# E77R.net
KiCad netlist of a schematic drawn in Altium Designer
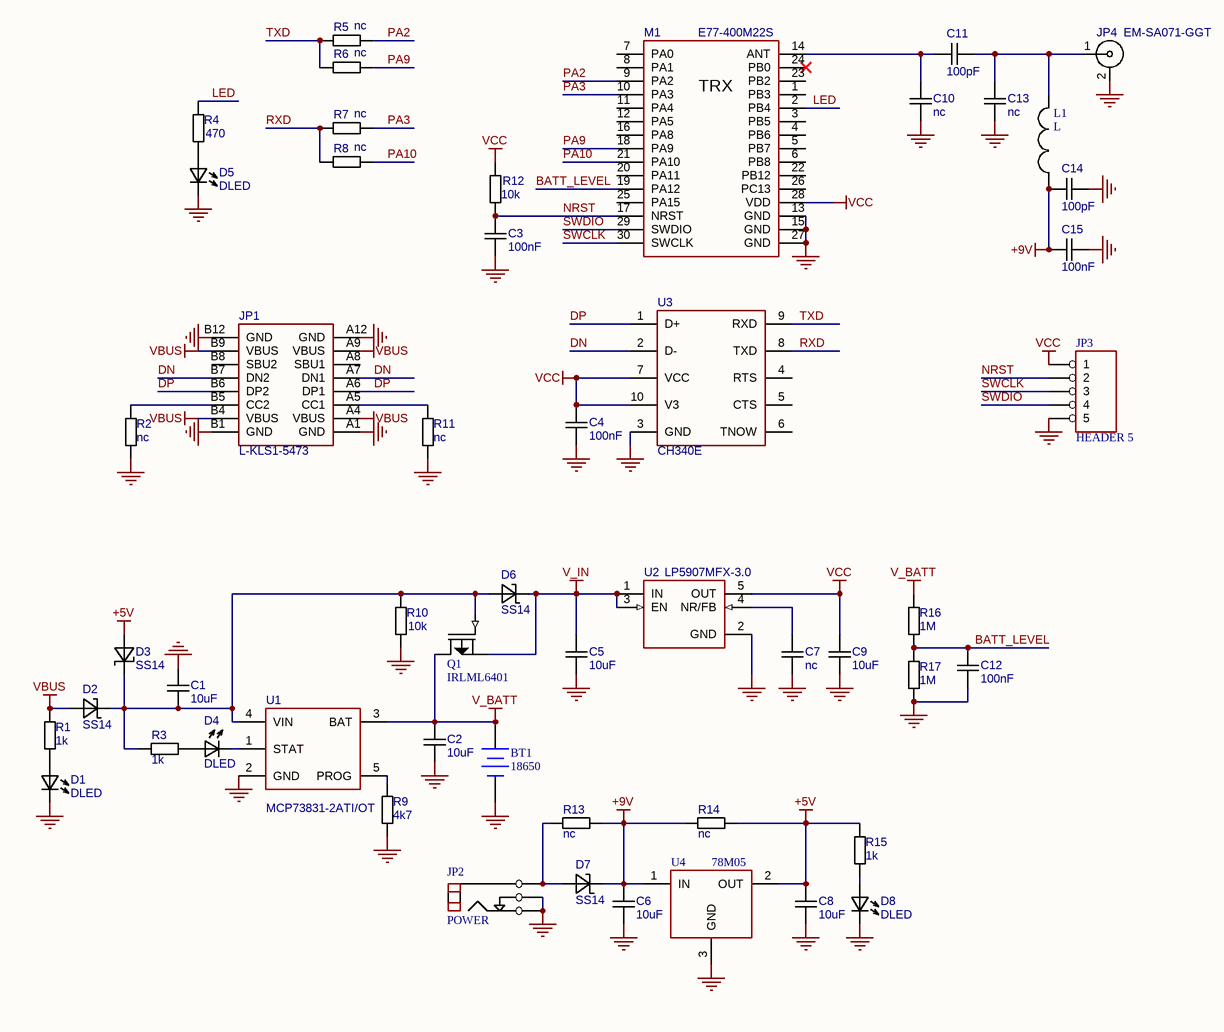
[diagram p0: E77R.SchDoc]

(export (version "E")
  (design (tool "Eeschema 10.0.6"))
  (components
    (comp (ref "BT1")
      (value "18650")
      (footprint "18650")
      (description "Multicell Battery")
      (fields (field (name "PUBLISHER") "Altium Limited"))
      (libsource (lib "zucker") (part "Battery"))
    )
    (comp (ref "C1")
      (value "10uF")
      (footprint "C-0805")
      (fields (field (name "VOLTAGE") "50V"))
      (libsource (lib "Passive") (part "CAPN"))
    )
    (comp (ref "C2")
      (value "10uF")
      (footprint "C-0805")
      (fields (field (name "VOLTAGE") "50V"))
      (libsource (lib "Passive") (part "CAPN"))
    )
    (comp (ref "C3")
      (value "100nF")
      (footprint "C-0603")
      (fields (field (name "VOLTAGE") "50V"))
      (libsource (lib "Passive") (part "CAPN"))
    )
    (comp (ref "C4")
      (value "100nF")
      (footprint "C-0603")
      (fields (field (name "VOLTAGE") "50V"))
      (libsource (lib "Passive") (part "CAPN"))
    )
    (comp (ref "C5")
      (value "10uF")
      (footprint "C-0805")
      (fields (field (name "VOLTAGE") "50V"))
      (libsource (lib "Passive") (part "CAPN"))
    )
    (comp (ref "C6")
      (value "10uF")
      (footprint "C-0805")
      (fields (field (name "VOLTAGE") "50V"))
      (libsource (lib "Passive") (part "CAPN"))
    )
    (comp (ref "C7")
      (value "nc")
      (footprint "C-0603")
      (fields (field (name "VOLTAGE") "50V"))
      (libsource (lib "Passive") (part "CAPN"))
    )
    (comp (ref "C8")
      (value "10uF")
      (footprint "C-0805")
      (fields (field (name "VOLTAGE") "50V"))
      (libsource (lib "Passive") (part "CAPN"))
    )
    (comp (ref "C9")
      (value "10uF")
      (footprint "C-0805")
      (fields (field (name "VOLTAGE") "50V"))
      (libsource (lib "Passive") (part "CAPN"))
    )
    (comp (ref "C10")
      (value "nc")
      (footprint "C-0603")
      (fields (field (name "VOLTAGE") "50V"))
      (libsource (lib "Passive") (part "CAPN"))
    )
    (comp (ref "C11")
      (value "100pF")
      (footprint "C-0603")
      (fields (field (name "VOLTAGE") "50V"))
      (libsource (lib "Passive") (part "CAPN"))
    )
    (comp (ref "C12")
      (value "100nF")
      (footprint "C-0603")
      (fields (field (name "VOLTAGE") "50V"))
      (libsource (lib "Passive") (part "CAPN"))
    )
    (comp (ref "C13")
      (value "nc")
      (footprint "C-0603")
      (fields (field (name "VOLTAGE") "50V"))
      (libsource (lib "Passive") (part "CAPN"))
    )
    (comp (ref "C14")
      (value "100pF")
      (footprint "C-0603")
      (fields (field (name "VOLTAGE") "50V"))
      (libsource (lib "Passive") (part "CAPN"))
    )
    (comp (ref "C15")
      (value "100nF")
      (footprint "C-0603")
      (fields (field (name "VOLTAGE") "50V"))
      (libsource (lib "Passive") (part "CAPN"))
    )
    (comp (ref "D1") (value "DLED") (footprint "LED0805") (libsource (lib "Diodes") (part "DLED")))
    (comp (ref "D2") (value "SS14") (footprint "D-SMA") (libsource (lib "Diodes") (part "DIODSH")))
    (comp (ref "D3") (value "SS14") (footprint "D-SMA") (libsource (lib "Diodes") (part "DIODSH")))
    (comp (ref "D4") (value "DLED") (footprint "LED0805") (libsource (lib "Diodes") (part "DLED")))
    (comp (ref "D5") (value "DLED") (footprint "LED0805") (libsource (lib "Diodes") (part "DLED")))
    (comp (ref "D6") (value "SS14") (footprint "D-SMA") (libsource (lib "Diodes") (part "DIODSH")))
    (comp (ref "D7") (value "SS14") (footprint "D-SMA") (libsource (lib "Diodes") (part "DIODSH")))
    (comp (ref "D8") (value "DLED") (footprint "LED0805") (libsource (lib "Diodes") (part "DLED")))
    (comp (ref "JP1")
      (value "L-KLS1-5473")
      (footprint "USB_C_SMD_SLOT")
      (libsource (lib "Connectors") (part "L-KLS1-5473"))
    )
    (comp (ref "JP2") (value "POWER") (footprint "DC-140-003") (libsource (lib "Connectors") (part "POWER")))
    (comp (ref "JP3")
      (value "HEADER 5")
      (footprint "PLS1-5")
      (libsource (lib "Connectors") (part "HEADER 5"))
    )
    (comp (ref "JP4")
      (value "EM-SA071-GGT")
      (footprint "SMA_F_EDGE")
      (description "SMA Female R/A PCB Mount")
      (libsource (lib "Connectors") (part "SMA"))
    )
    (comp (ref "L1") (value "L") (footprint "SCI1812") (libsource (lib "Passive") (part "L")))
    (comp (ref "M1")
      (value "E77-400M22S")
      (footprint "E77XX-M22")
      (libsource (lib "RFmodules") (part "E77-400M22S"))
    )
    (comp (ref "Q1") (value "IRLML6401") (footprint "SOT-23") (libsource (lib "Discrete") (part "MOSF-P")))
    (comp (ref "R1") (value "1k") (footprint "R-0603") (libsource (lib "") (part "RES_1")))
    (comp (ref "R2") (value "nc") (footprint "R-0603") (libsource (lib "") (part "RES_3")))
    (comp (ref "R3") (value "1k") (footprint "R-0603") (libsource (lib "") (part "RES_2")))
    (comp (ref "R4") (value "470") (footprint "R-0603") (libsource (lib "") (part "RES_1")))
    (comp (ref "R5") (value "nc") (footprint "R-0603") (libsource (lib "Passive") (part "RES")))
    (comp (ref "R6") (value "nc") (footprint "R-0603") (libsource (lib "Passive") (part "RES")))
    (comp (ref "R7") (value "nc") (footprint "R-0603") (libsource (lib "Passive") (part "RES")))
    (comp (ref "R8") (value "nc") (footprint "R-0603") (libsource (lib "Passive") (part "RES")))
    (comp (ref "R9") (value "4k7") (footprint "R-0603") (libsource (lib "") (part "RES_1")))
    (comp (ref "R10") (value "10k") (footprint "R-0603") (libsource (lib "") (part "RES_1")))
    (comp (ref "R11") (value "nc") (footprint "R-0603") (libsource (lib "") (part "RES_3")))
    (comp (ref "R12") (value "10k") (footprint "R-0603") (libsource (lib "") (part "RES_1")))
    (comp (ref "R13") (value "nc") (footprint "R-0805") (libsource (lib "Passive") (part "RES")))
    (comp (ref "R14") (value "nc") (footprint "R-0805") (libsource (lib "Passive") (part "RES")))
    (comp (ref "R15") (value "1k") (footprint "R-0603") (libsource (lib "") (part "RES_1")))
    (comp (ref "R16") (value "1M") (footprint "R-0603") (libsource (lib "") (part "RES_1")))
    (comp (ref "R17") (value "1M") (footprint "R-0603") (libsource (lib "") (part "RES_1")))
    (comp (ref "U1")
      (value "MCP73831-2ATI/OT")
      (footprint "SOT-23-5")
      (fields
        (field (name "LIBRARY PART") "IC`s.SchLib")
        (field (name "FOOTPRINT PART") "IC-package.PcbLib")
        (field (name "MANUFACTURER") "Texas Instruments")
      )
      (libsource (lib "ICs") (part "MCP73831-2ATI/OT"))
    )
    (comp (ref "U2")
      (value "LP5907MFX-3.0")
      (footprint "SOT-23-5")
      (description "250mA Low-Dropout Regulator")
      (libsource (lib "ICs") (part "LP5907"))
    )
    (comp (ref "U3") (value "CH340E") (footprint "MSOP-10") (libsource (lib "ICs") (part "CH340E")))
    (comp (ref "U4") (value "78M05") (footprint "DPAK3") (libsource (lib "ICs") (part "78M08")))
  )
  (nets
    (net (code "1") (name "+5V") (class "Default")
      (node (ref "C8") (pin "1") (pinfunction "1_1") (pintype "passive"))
      (node (ref "D3") (pin "1") (pinfunction "1_1") (pintype "passive"))
      (node (ref "R14") (pin "1") (pinfunction "1_1") (pintype "passive"))
      (node (ref "R15") (pin "2") (pinfunction "2_2") (pintype "passive"))
      (node (ref "U4") (pin "2") (pinfunction "OUT_2") (pintype "passive"))
    )
    (net (code "2") (name "+9V") (class "Default")
      (node (ref "C14") (pin "1") (pinfunction "1_1") (pintype "passive"))
      (node (ref "C15") (pin "2") (pinfunction "2_2") (pintype "passive"))
      (node (ref "C6") (pin "1") (pinfunction "1_1") (pintype "passive"))
      (node (ref "D7") (pin "2") (pinfunction "2_2") (pintype "passive"))
      (node (ref "L1") (pin "1") (pinfunction "1_1") (pintype "passive"))
      (node (ref "R13") (pin "1") (pinfunction "1_1") (pintype "passive"))
      (node (ref "R14") (pin "2") (pinfunction "2_2") (pintype "passive"))
      (node (ref "U4") (pin "1") (pinfunction "IN_1") (pintype "passive"))
    )
    (net (code "3") (name "/BATT_LEVEL") (class "Default")
      (node (ref "C12") (pin "2") (pinfunction "2_2") (pintype "passive"))
      (node (ref "M1") (pin "19") (pinfunction "PA12_19") (pintype "passive"))
      (node (ref "R16") (pin "1") (pinfunction "1_1") (pintype "passive"))
      (node (ref "R17") (pin "2") (pinfunction "2_2") (pintype "passive"))
    )
    (net (code "4") (name "/DN") (class "Default")
      (node (ref "JP1") (pin "A7") (pinfunction "DN1_A7") (pintype "passive"))
      (node (ref "JP1") (pin "B7") (pinfunction "DN2_B7") (pintype "passive"))
      (node (ref "U3") (pin "2") (pinfunction "D-_2") (pintype "passive"))
    )
    (net (code "5") (name "/DP") (class "Default")
      (node (ref "JP1") (pin "A6") (pinfunction "DP1_A6") (pintype "passive"))
      (node (ref "JP1") (pin "B6") (pinfunction "DP2_B6") (pintype "passive"))
      (node (ref "U3") (pin "1") (pinfunction "D+_1") (pintype "passive"))
    )
    (net (code "6") (name "/LED") (class "Default")
      (node (ref "M1") (pin "2") (pinfunction "PB4_2") (pintype "passive"))
      (node (ref "R4") (pin "2") (pinfunction "2_2") (pintype "passive"))
    )
    (net (code "7") (name "/NRST") (class "Default")
      (node (ref "C3") (pin "2") (pinfunction "2_2") (pintype "passive"))
      (node (ref "JP3") (pin "2") (pinfunction "2_2") (pintype "passive"))
      (node (ref "M1") (pin "17") (pinfunction "NRST_17") (pintype "passive"))
      (node (ref "R12") (pin "1") (pinfunction "1_1") (pintype "passive"))
    )
    (net (code "8") (name "/PA2") (class "Default")
      (node (ref "M1") (pin "9") (pinfunction "PA2_9") (pintype "passive"))
      (node (ref "R5") (pin "1") (pinfunction "1_1") (pintype "passive"))
    )
    (net (code "9") (name "/PA3") (class "Default")
      (node (ref "M1") (pin "10") (pinfunction "PA3_10") (pintype "passive"))
      (node (ref "R7") (pin "1") (pinfunction "1_1") (pintype "passive"))
    )
    (net (code "10") (name "/PA9") (class "Default")
      (node (ref "M1") (pin "18") (pinfunction "PA9_18") (pintype "passive"))
      (node (ref "R6") (pin "1") (pinfunction "1_1") (pintype "passive"))
    )
    (net (code "11") (name "/PA10") (class "Default")
      (node (ref "M1") (pin "21") (pinfunction "PA10_21") (pintype "passive"))
      (node (ref "R8") (pin "1") (pinfunction "1_1") (pintype "passive"))
    )
    (net (code "12") (name "/RXD") (class "Default")
      (node (ref "R7") (pin "2") (pinfunction "2_2") (pintype "passive"))
      (node (ref "R8") (pin "2") (pinfunction "2_2") (pintype "passive"))
      (node (ref "U3") (pin "8") (pinfunction "TXD_8") (pintype "passive"))
    )
    (net (code "13") (name "/SWCLK") (class "Default")
      (node (ref "JP3") (pin "3") (pinfunction "3_3") (pintype "passive"))
      (node (ref "M1") (pin "30") (pinfunction "SWCLK_30") (pintype "passive"))
    )
    (net (code "14") (name "/SWDIO") (class "Default")
      (node (ref "JP3") (pin "4") (pinfunction "4_4") (pintype "passive"))
      (node (ref "M1") (pin "29") (pinfunction "SWDIO_29") (pintype "passive"))
    )
    (net (code "15") (name "/TXD") (class "Default")
      (node (ref "R5") (pin "2") (pinfunction "2_2") (pintype "passive"))
      (node (ref "R6") (pin "2") (pinfunction "2_2") (pintype "passive"))
      (node (ref "U3") (pin "9") (pinfunction "RXD_9") (pintype "passive"))
    )
    (net (code "16") (name "GND") (class "Default")
      (node (ref "BT1") (pin "2") (pinfunction "-_2") (pintype "passive"))
      (node (ref "C1") (pin "2") (pinfunction "2_2") (pintype "passive"))
      (node (ref "C10") (pin "1") (pinfunction "1_1") (pintype "passive"))
      (node (ref "C12") (pin "1") (pinfunction "1_1") (pintype "passive"))
      (node (ref "C13") (pin "1") (pinfunction "1_1") (pintype "passive"))
      (node (ref "C14") (pin "2") (pinfunction "2_2") (pintype "passive"))
      (node (ref "C15") (pin "1") (pinfunction "1_1") (pintype "passive"))
      (node (ref "C2") (pin "1") (pinfunction "1_1") (pintype "passive"))
      (node (ref "C3") (pin "1") (pinfunction "1_1") (pintype "passive"))
      (node (ref "C4") (pin "1") (pinfunction "1_1") (pintype "passive"))
      (node (ref "C5") (pin "2") (pinfunction "2_2") (pintype "passive"))
      (node (ref "C6") (pin "2") (pinfunction "2_2") (pintype "passive"))
      (node (ref "C7") (pin "2") (pinfunction "2_2") (pintype "passive"))
      (node (ref "C8") (pin "2") (pinfunction "2_2") (pintype "passive"))
      (node (ref "C9") (pin "2") (pinfunction "2_2") (pintype "passive"))
      (node (ref "D1") (pin "2") (pinfunction "2_2") (pintype "passive"))
      (node (ref "D5") (pin "2") (pinfunction "2_2") (pintype "passive"))
      (node (ref "D8") (pin "2") (pinfunction "2_2") (pintype "passive"))
      (node (ref "JP1") (pin "A1") (pinfunction "GND_A1") (pintype "passive"))
      (node (ref "JP1") (pin "A12") (pinfunction "GND_A12") (pintype "passive"))
      (node (ref "JP1") (pin "B1") (pinfunction "GND_B1") (pintype "passive"))
      (node (ref "JP1") (pin "B12") (pinfunction "GND_B12") (pintype "passive"))
      (node (ref "JP2") (pin "2") (pinfunction "C_2") (pintype "passive"))
      (node (ref "JP2") (pin "3") (pinfunction "B_3") (pintype "passive"))
      (node (ref "JP3") (pin "5") (pinfunction "5_5") (pintype "passive"))
      (node (ref "JP4") (pin "2") (pinfunction "2_2") (pintype "passive"))
      (node (ref "M1") (pin "13") (pinfunction "GND_13") (pintype "passive"))
      (node (ref "M1") (pin "15") (pinfunction "GND_15") (pintype "passive"))
      (node (ref "M1") (pin "27") (pinfunction "GND_27") (pintype "passive"))
      (node (ref "R10") (pin "1") (pinfunction "1_1") (pintype "passive"))
      (node (ref "R11") (pin "2") (pinfunction "2_2") (pintype "passive"))
      (node (ref "R17") (pin "1") (pinfunction "1_1") (pintype "passive"))
      (node (ref "R2") (pin "2") (pinfunction "2_2") (pintype "passive"))
      (node (ref "R9") (pin "1") (pinfunction "1_1") (pintype "passive"))
      (node (ref "U1") (pin "2") (pinfunction "GND_2") (pintype "passive"))
      (node (ref "U2") (pin "2") (pinfunction "GND_2") (pintype "power_in"))
      (node (ref "U3") (pin "3") (pinfunction "GND_3") (pintype "passive"))
      (node (ref "U4") (pin "3") (pinfunction "GND_3") (pintype "passive"))
    )
    (net (code "17") (name "Net-(C11-Pad2)") (class "Default")
      (node (ref "C11") (pin "2") (pinfunction "2_2") (pintype "passive"))
      (node (ref "C13") (pin "2") (pinfunction "2_2") (pintype "passive"))
      (node (ref "JP4") (pin "1") (pinfunction "1_1") (pintype "passive"))
      (node (ref "L1") (pin "2") (pinfunction "2_2") (pintype "passive"))
    )
    (net (code "18") (name "Net-(D1-Pad1)") (class "Default")
      (node (ref "D1") (pin "1") (pinfunction "1_1") (pintype "passive"))
      (node (ref "R1") (pin "1") (pinfunction "1_1") (pintype "passive"))
    )
    (net (code "19") (name "Net-(D4-Pad1)") (class "Default")
      (node (ref "D4") (pin "1") (pinfunction "1_1") (pintype "passive"))
      (node (ref "R3") (pin "2") (pinfunction "2_2") (pintype "passive"))
    )
    (net (code "20") (name "Net-(D5-Pad1)") (class "Default")
      (node (ref "D5") (pin "1") (pinfunction "1_1") (pintype "passive"))
      (node (ref "R4") (pin "1") (pinfunction "1_1") (pintype "passive"))
    )
    (net (code "21") (name "Net-(D8-Pad1)") (class "Default")
      (node (ref "D8") (pin "1") (pinfunction "1_1") (pintype "passive"))
      (node (ref "R15") (pin "1") (pinfunction "1_1") (pintype "passive"))
    )
    (net (code "22") (name "Net-(JP1-CC1)") (class "Default")
      (node (ref "JP1") (pin "A5") (pinfunction "CC1_A5") (pintype "passive"))
      (node (ref "R11") (pin "1") (pinfunction "1_1") (pintype "passive"))
    )
    (net (code "23") (name "Net-(JP1-CC2)") (class "Default")
      (node (ref "JP1") (pin "B5") (pinfunction "CC2_B5") (pintype "passive"))
      (node (ref "R2") (pin "1") (pinfunction "1_1") (pintype "passive"))
    )
    (net (code "24") (name "Net-(JP2-A)") (class "Default")
      (node (ref "D7") (pin "1") (pinfunction "1_1") (pintype "passive"))
      (node (ref "JP2") (pin "1") (pinfunction "A_1") (pintype "passive"))
      (node (ref "R13") (pin "2") (pinfunction "2_2") (pintype "passive"))
    )
    (net (code "25") (name "Net-(M1-ANT)") (class "Default")
      (node (ref "C10") (pin "2") (pinfunction "2_2") (pintype "passive"))
      (node (ref "C11") (pin "1") (pinfunction "1_1") (pintype "passive"))
      (node (ref "M1") (pin "14") (pinfunction "ANT_14") (pintype "passive"))
    )
    (net (code "26") (name "Net-(Q1-GATE)") (class "Default")
      (node (ref "C1") (pin "1") (pinfunction "1_1") (pintype "passive"))
      (node (ref "D2") (pin "2") (pinfunction "2_2") (pintype "passive"))
      (node (ref "D3") (pin "2") (pinfunction "2_2") (pintype "passive"))
      (node (ref "D6") (pin "1") (pinfunction "1_1") (pintype "passive"))
      (node (ref "Q1") (pin "1") (pinfunction "GATE_1") (pintype "input"))
      (node (ref "R10") (pin "2") (pinfunction "2_2") (pintype "passive"))
      (node (ref "R3") (pin "1") (pinfunction "1_1") (pintype "passive"))
      (node (ref "U1") (pin "4") (pinfunction "VIN_4") (pintype "passive"))
    )
    (net (code "27") (name "Net-(U1-PROG)") (class "Default")
      (node (ref "R9") (pin "2") (pinfunction "2_2") (pintype "passive"))
      (node (ref "U1") (pin "5") (pinfunction "PROG_5") (pintype "passive"))
    )
    (net (code "28") (name "Net-(U1-STAT)") (class "Default")
      (node (ref "D4") (pin "2") (pinfunction "2_2") (pintype "passive"))
      (node (ref "U1") (pin "1") (pinfunction "STAT_1") (pintype "passive"))
    )
    (net (code "29") (name "Net-(U2-NR{slash}FB)") (class "Default")
      (node (ref "C7") (pin "1") (pinfunction "1_1") (pintype "passive"))
      (node (ref "U2") (pin "4") (pinfunction "NR/FB_4") (pintype "input"))
    )
    (net (code "30") (name "VBUS") (class "Default")
      (node (ref "D2") (pin "1") (pinfunction "1_1") (pintype "passive"))
      (node (ref "JP1") (pin "A4") (pinfunction "VBUS_A4") (pintype "passive"))
      (node (ref "JP1") (pin "A9") (pinfunction "VBUS_A9") (pintype "passive"))
      (node (ref "JP1") (pin "B4") (pinfunction "VBUS_B4") (pintype "passive"))
      (node (ref "JP1") (pin "B9") (pinfunction "VBUS_B9") (pintype "passive"))
      (node (ref "R1") (pin "2") (pinfunction "2_2") (pintype "passive"))
    )
    (net (code "31") (name "VCC") (class "Default")
      (node (ref "C4") (pin "2") (pinfunction "2_2") (pintype "passive"))
      (node (ref "C9") (pin "1") (pinfunction "1_1") (pintype "passive"))
      (node (ref "JP3") (pin "1") (pinfunction "1_1") (pintype "passive"))
      (node (ref "M1") (pin "28") (pinfunction "VDD_28") (pintype "passive"))
      (node (ref "R12") (pin "2") (pinfunction "2_2") (pintype "passive"))
      (node (ref "U2") (pin "5") (pinfunction "OUT_5") (pintype "power_in"))
      (node (ref "U3") (pin "10") (pinfunction "V3_10") (pintype "passive"))
      (node (ref "U3") (pin "7") (pinfunction "VCC_7") (pintype "passive"))
    )
    (net (code "32") (name "VSS") (class "Default")
      (node (ref "JP1") (pin "17") (pinfunction "VSS_17") (pintype "power_in"))
    )
    (net (code "33") (name "V_BATT") (class "Default")
      (node (ref "BT1") (pin "1") (pinfunction "+_1") (pintype "passive"))
      (node (ref "C2") (pin "2") (pinfunction "2_2") (pintype "passive"))
      (node (ref "Q1") (pin "3") (pinfunction "DRAIN_3") (pintype "passive"))
      (node (ref "R16") (pin "2") (pinfunction "2_2") (pintype "passive"))
      (node (ref "U1") (pin "3") (pinfunction "BAT_3") (pintype "passive"))
    )
    (net (code "34") (name "V_IN") (class "Default")
      (node (ref "C5") (pin "1") (pinfunction "1_1") (pintype "passive"))
      (node (ref "D6") (pin "2") (pinfunction "2_2") (pintype "passive"))
      (node (ref "Q1") (pin "2") (pinfunction "SOURCE_2") (pintype "passive"))
      (node (ref "U2") (pin "1") (pinfunction "IN_1") (pintype "power_in"))
      (node (ref "U2") (pin "3") (pinfunction "EN_3") (pintype "input"))
    )
    (net (code "35") (name "unconnected-(JP1-SBU1-PadA8)") (class "Default")
      (node (ref "JP1") (pin "A8") (pinfunction "SBU1_A8") (pintype "passive"))
    )
    (net (code "36") (name "unconnected-(JP1-SBU2-PadB8)") (class "Default")
      (node (ref "JP1") (pin "B8") (pinfunction "SBU2_B8") (pintype "passive"))
    )
    (net (code "37") (name "unconnected-(M1-PA0-Pad7)") (class "Default")
      (node (ref "M1") (pin "7") (pinfunction "PA0_7") (pintype "passive"))
    )
    (net (code "38") (name "unconnected-(M1-PA1-Pad8)") (class "Default")
      (node (ref "M1") (pin "8") (pinfunction "PA1_8") (pintype "passive"))
    )
    (net (code "39") (name "unconnected-(M1-PA4-Pad11)") (class "Default")
      (node (ref "M1") (pin "11") (pinfunction "PA4_11") (pintype "passive"))
    )
    (net (code "40") (name "unconnected-(M1-PA5-Pad12)") (class "Default")
      (node (ref "M1") (pin "12") (pinfunction "PA5_12") (pintype "passive"))
    )
    (net (code "41") (name "unconnected-(M1-PA8-Pad16)") (class "Default")
      (node (ref "M1") (pin "16") (pinfunction "PA8_16") (pintype "passive"))
    )
    (net (code "42") (name "unconnected-(M1-PA11-Pad20)") (class "Default")
      (node (ref "M1") (pin "20") (pinfunction "PA11_20") (pintype "passive"))
    )
    (net (code "43") (name "unconnected-(M1-PA15-Pad25)") (class "Default")
      (node (ref "M1") (pin "25") (pinfunction "PA15_25") (pintype "passive"))
    )
    (net (code "44") (name "unconnected-(M1-PB0-Pad24)") (class "Default")
      (node (ref "M1") (pin "24") (pinfunction "PB0_24") (pintype "passive+no_connect"))
    )
    (net (code "45") (name "unconnected-(M1-PB2-Pad23)") (class "Default")
      (node (ref "M1") (pin "23") (pinfunction "PB2_23") (pintype "passive"))
    )
    (net (code "46") (name "unconnected-(M1-PB3-Pad1)") (class "Default")
      (node (ref "M1") (pin "1") (pinfunction "PB3_1") (pintype "passive"))
    )
    (net (code "47") (name "unconnected-(M1-PB5-Pad3)") (class "Default")
      (node (ref "M1") (pin "3") (pinfunction "PB5_3") (pintype "passive"))
    )
    (net (code "48") (name "unconnected-(M1-PB6-Pad4)") (class "Default")
      (node (ref "M1") (pin "4") (pinfunction "PB6_4") (pintype "passive"))
    )
    (net (code "49") (name "unconnected-(M1-PB7-Pad5)") (class "Default")
      (node (ref "M1") (pin "5") (pinfunction "PB7_5") (pintype "passive"))
    )
    (net (code "50") (name "unconnected-(M1-PB8-Pad6)") (class "Default")
      (node (ref "M1") (pin "6") (pinfunction "PB8_6") (pintype "passive"))
    )
    (net (code "51") (name "unconnected-(M1-PB12-Pad22)") (class "Default")
      (node (ref "M1") (pin "22") (pinfunction "PB12_22") (pintype "passive"))
    )
    (net (code "52") (name "unconnected-(M1-PC13-Pad26)") (class "Default")
      (node (ref "M1") (pin "26") (pinfunction "PC13_26") (pintype "passive"))
    )
    (net (code "53") (name "unconnected-(U3-CTS-Pad5)") (class "Default")
      (node (ref "U3") (pin "5") (pinfunction "CTS_5") (pintype "passive"))
    )
    (net (code "54") (name "unconnected-(U3-RTS-Pad4)") (class "Default")
      (node (ref "U3") (pin "4") (pinfunction "RTS_4") (pintype "passive"))
    )
    (net (code "55") (name "unconnected-(U3-TNOW-Pad6)") (class "Default")
      (node (ref "U3") (pin "6") (pinfunction "TNOW_6") (pintype "passive"))
    )
  )
)
